# 5_USB3.net
KiCad netlist of a schematic drawn in Altium Designer
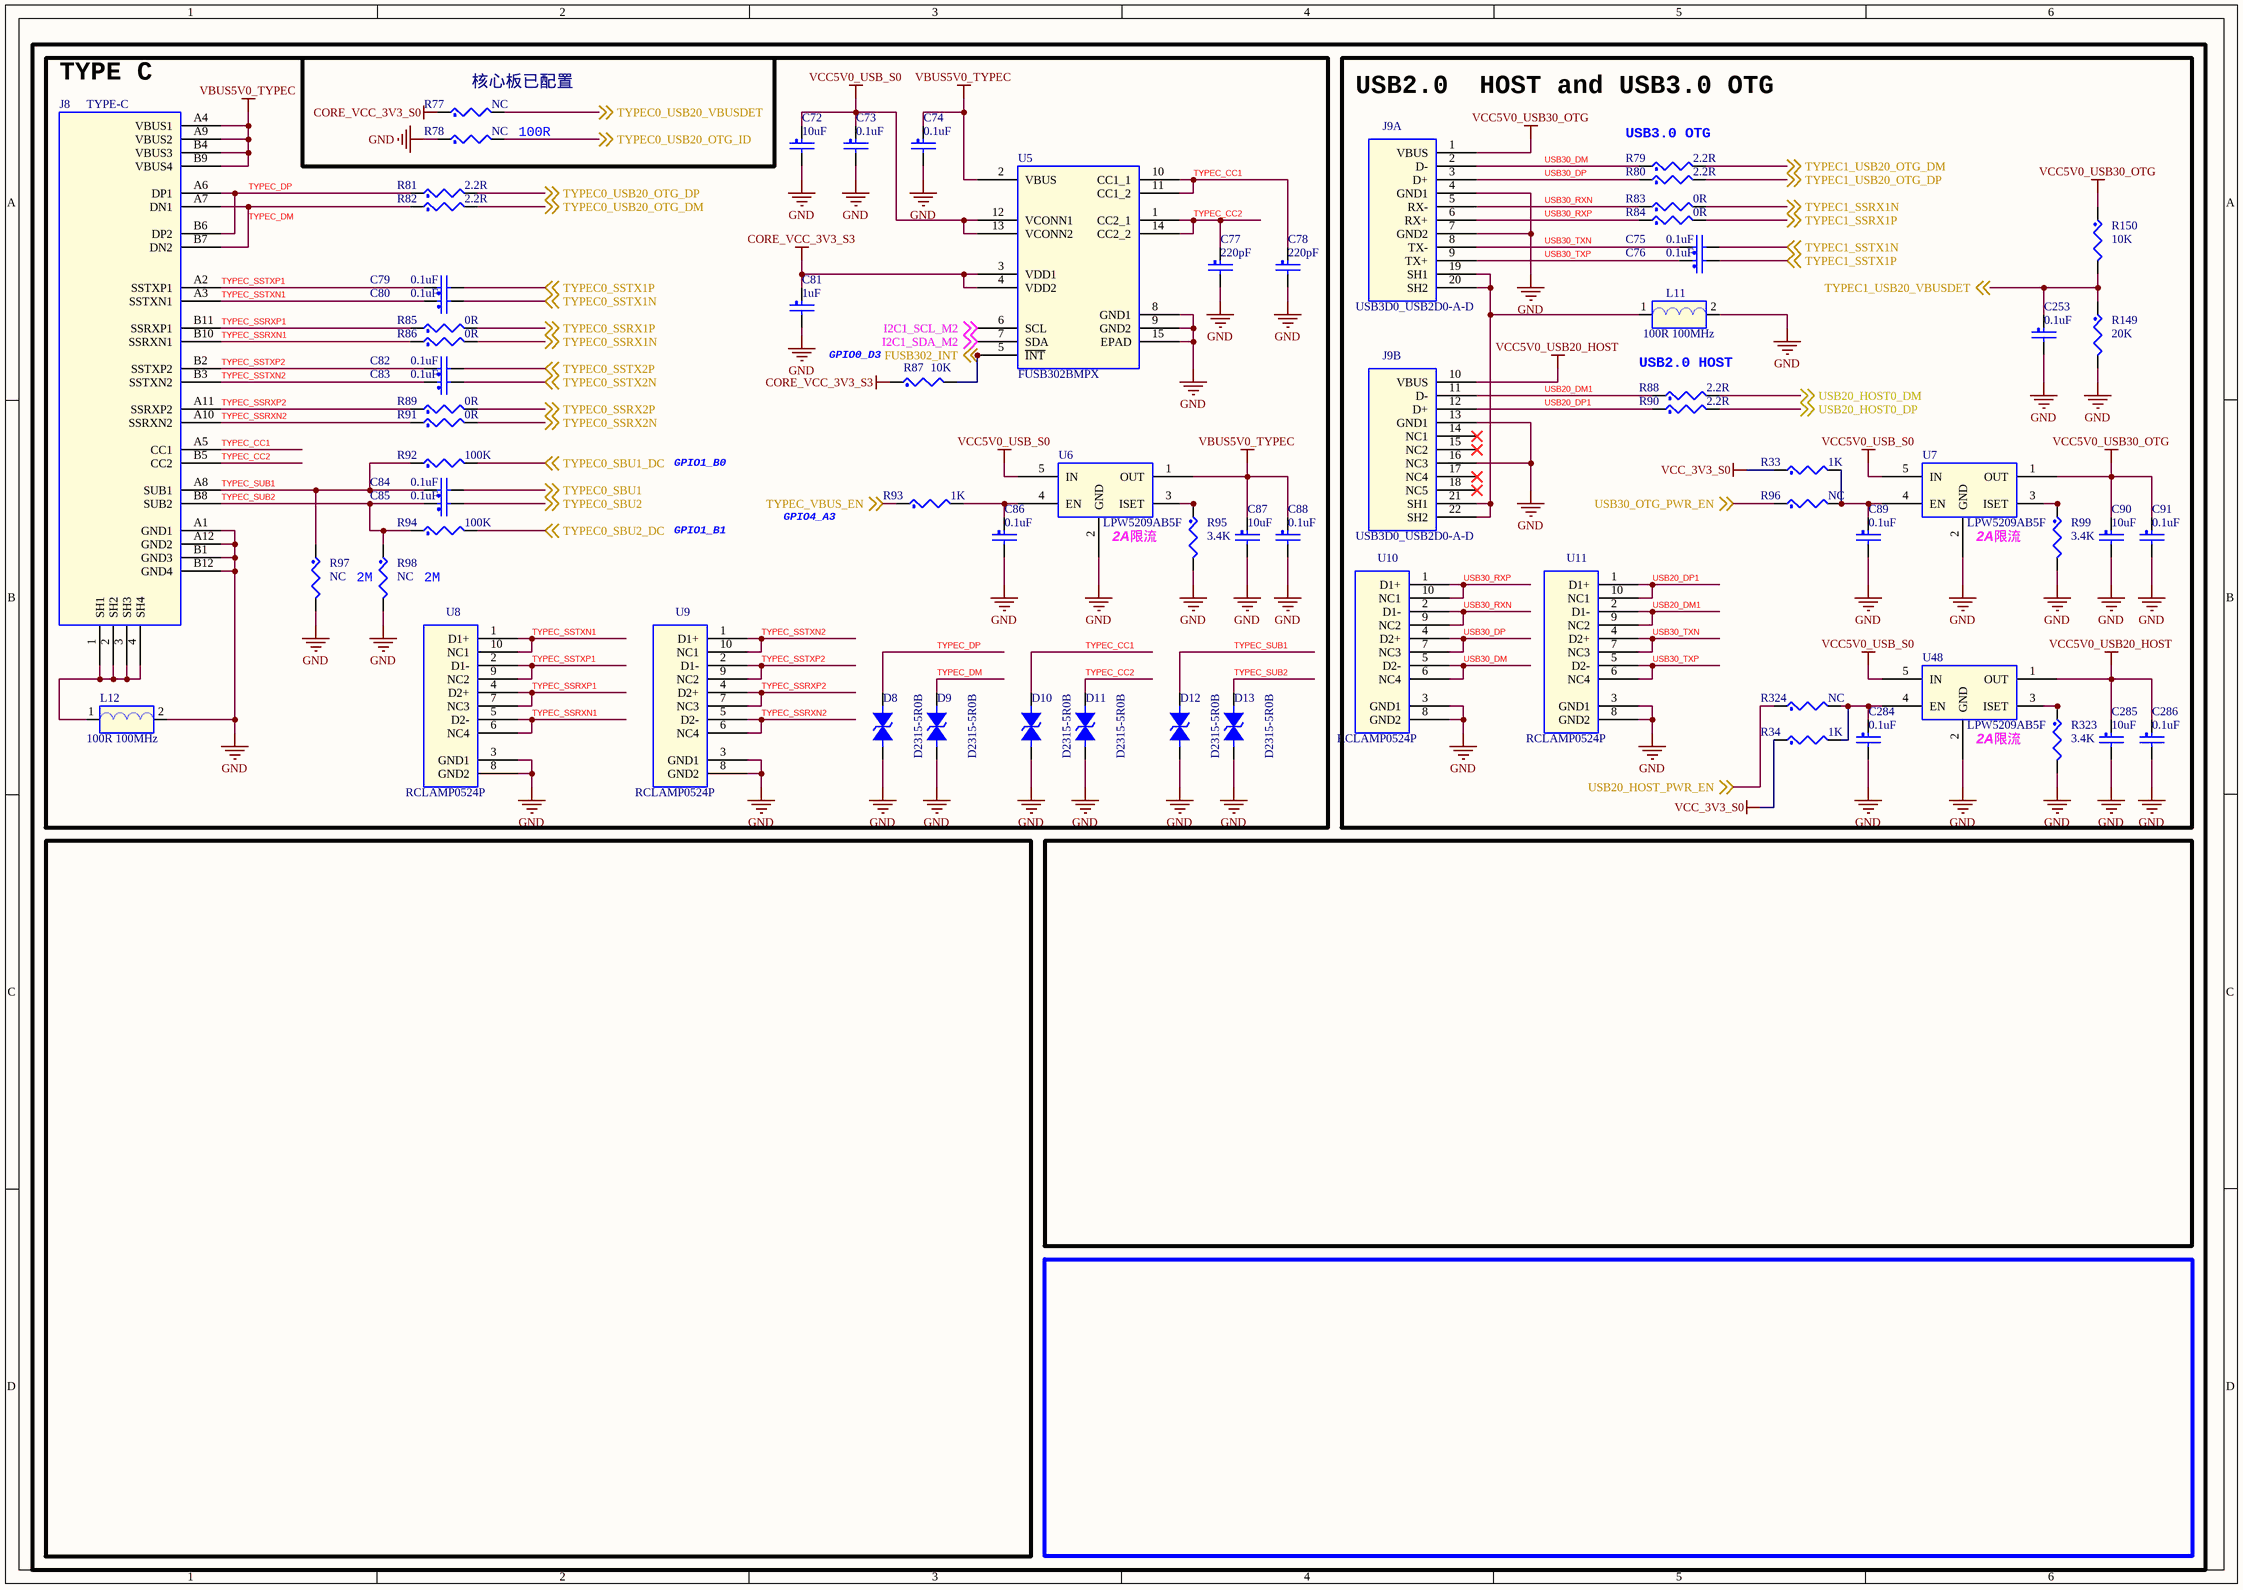
[diagram p0: 5.USB3.SchDoc]

(export (version "E")
  (design (tool "Eeschema 10.0.6"))
  (components
    (comp (ref "C72") (value "10uF") (footprint "0.PCB1:C0402") (libsource (lib "RK3588底板") (part "CAP_NP")))
    (comp (ref "C73") (value "0.1uF") (footprint "0.PCB1:C0402") (libsource (lib "RK3588底板") (part "CAP_NP")))
    (comp (ref "C74") (value "0.1uF") (footprint "0.PCB1:C0402") (libsource (lib "RK3588底板") (part "CAP_NP")))
    (comp (ref "C75") (value "0.1uF") (footprint "0.PCB1:C0402") (libsource (lib "RK3588底板") (part "CAP_NP")))
    (comp (ref "C76") (value "0.1uF") (footprint "0.PCB1:C0402") (libsource (lib "RK3588底板") (part "CAP_NP")))
    (comp (ref "C77") (value "220pF") (footprint "0.PCB1:C0402") (libsource (lib "RK3588底板") (part "CAP_NP")))
    (comp (ref "C78") (value "220pF") (footprint "0.PCB1:C0402") (libsource (lib "RK3588底板") (part "CAP_NP")))
    (comp (ref "C79") (value "0.1uF") (footprint "0.PCB1:C0402") (libsource (lib "RK3588底板") (part "CAP_NP")))
    (comp (ref "C80") (value "0.1uF") (footprint "0.PCB1:C0402") (libsource (lib "RK3588底板") (part "CAP_NP")))
    (comp (ref "C81") (value "1uF") (footprint "0.PCB1:C0402") (libsource (lib "RK3588底板") (part "CAP_NP")))
    (comp (ref "C82") (value "0.1uF") (footprint "0.PCB1:C0402") (libsource (lib "RK3588底板") (part "CAP_NP")))
    (comp (ref "C83") (value "0.1uF") (footprint "0.PCB1:C0402") (libsource (lib "RK3588底板") (part "CAP_NP")))
    (comp (ref "C84") (value "0.1uF") (footprint "0.PCB1:C0402") (libsource (lib "RK3588底板") (part "CAP_NP")))
    (comp (ref "C85") (value "0.1uF") (footprint "0.PCB1:C0402") (libsource (lib "RK3588底板") (part "CAP_NP")))
    (comp (ref "C86") (value "0.1uF") (footprint "0.PCB1:C0402") (libsource (lib "RK3588底板") (part "CAP_NP")))
    (comp (ref "C87") (value "10uF") (footprint "0.PCB1:C0402") (libsource (lib "RK3588底板") (part "CAP_NP")))
    (comp (ref "C88") (value "0.1uF") (footprint "0.PCB1:C0402") (libsource (lib "RK3588底板") (part "CAP_NP")))
    (comp (ref "C89") (value "0.1uF") (footprint "0.PCB1:C0402") (libsource (lib "RK3588底板") (part "CAP_NP")))
    (comp (ref "C90") (value "10uF") (footprint "0.PCB1:C0402") (libsource (lib "RK3588底板") (part "CAP_NP")))
    (comp (ref "C91") (value "0.1uF") (footprint "0.PCB1:C0402") (libsource (lib "RK3588底板") (part "CAP_NP")))
    (comp (ref "C253")
      (value "0.1uF")
      (footprint "0.PCB1:C0402")
      (libsource (lib "RK3588底板") (part "CAP_NP"))
    )
    (comp (ref "C284")
      (value "0.1uF")
      (footprint "0.PCB1:C0402")
      (libsource (lib "RK3588底板") (part "CAP_NP"))
    )
    (comp (ref "C285") (value "10uF") (footprint "0.PCB1:C0402") (libsource (lib "RK3588底板") (part "CAP_NP")))
    (comp (ref "C286")
      (value "0.1uF")
      (footprint "0.PCB1:C0402")
      (libsource (lib "RK3588底板") (part "CAP_NP"))
    )
    (comp (ref "D8")
      (value "D2315-5R0B")
      (footprint "0.PCB1:esd0402")
      (libsource (lib "RK3588底板") (part "DIODE BI-DIR TRIG"))
    )
    (comp (ref "D9")
      (value "D2315-5R0B")
      (footprint "0.PCB1:esd0402")
      (libsource (lib "RK3588底板") (part "DIODE BI-DIR TRIG"))
    )
    (comp (ref "D10")
      (value "D2315-5R0B")
      (footprint "0.PCB1:esd0402")
      (libsource (lib "RK3588底板") (part "DIODE BI-DIR TRIG"))
    )
    (comp (ref "D11")
      (value "D2315-5R0B")
      (footprint "0.PCB1:esd0402")
      (libsource (lib "RK3588底板") (part "DIODE BI-DIR TRIG"))
    )
    (comp (ref "D12")
      (value "D2315-5R0B")
      (footprint "0.PCB1:esd0402")
      (libsource (lib "RK3588底板") (part "DIODE BI-DIR TRIG"))
    )
    (comp (ref "D13")
      (value "D2315-5R0B")
      (footprint "0.PCB1:esd0402")
      (libsource (lib "RK3588底板") (part "DIODE BI-DIR TRIG"))
    )
    (comp (ref "J8")
      (value "TYPE-C")
      (footprint "0.PCB1:usb-c-smd_tyc-324g")
      (libsource (lib "RK3588底板") (part "TYPE-C-24P"))
    )
    (comp (ref "J9")
      (value "USB3D0_USB2D0-A-D")
      (footprint "0.PCB1:USB3D0-AF-18P")
      (libsource (lib "RK3588底板") (part "USB3D0_USB2D0-A-D"))
    )
    (comp (ref "L11")
      (value "100R 100MHz")
      (footprint "0.PCB1:L0603")
      (libsource (lib "RK3588底板") (part "BEAD"))
    )
    (comp (ref "L12")
      (value "100R 100MHz")
      (footprint "0.PCB1:L0603")
      (libsource (lib "RK3588底板") (part "BEAD"))
    )
    (comp (ref "R33") (value "1K") (footprint "0.PCB1:R0402") (libsource (lib "RK3588底板") (part "RES")))
    (comp (ref "R34") (value "1K") (footprint "0.PCB1:R0402") (libsource (lib "RK3588底板") (part "RES")))
    (comp (ref "R77") (value "NC") (footprint "0.PCB1:R0402") (libsource (lib "RK3588底板") (part "RES")))
    (comp (ref "R78") (value "NC") (footprint "0.PCB1:R0402") (libsource (lib "RK3588底板") (part "RES")))
    (comp (ref "R79") (value "2.2R") (footprint "0.PCB1:R0402") (libsource (lib "RK3588底板") (part "RES")))
    (comp (ref "R80") (value "2.2R") (footprint "0.PCB1:R0402") (libsource (lib "RK3588底板") (part "RES")))
    (comp (ref "R81") (value "2.2R") (footprint "0.PCB1:R0402") (libsource (lib "RK3588底板") (part "RES")))
    (comp (ref "R82") (value "2.2R") (footprint "0.PCB1:R0402") (libsource (lib "RK3588底板") (part "RES")))
    (comp (ref "R83") (value "0R") (footprint "0.PCB1:R0402") (libsource (lib "RK3588底板") (part "RES")))
    (comp (ref "R84") (value "0R") (footprint "0.PCB1:R0402") (libsource (lib "RK3588底板") (part "RES")))
    (comp (ref "R85") (value "0R") (footprint "0.PCB1:R0402") (libsource (lib "RK3588底板") (part "RES")))
    (comp (ref "R86") (value "0R") (footprint "0.PCB1:R0402") (libsource (lib "RK3588底板") (part "RES")))
    (comp (ref "R87") (value "10K") (footprint "0.PCB1:R0402") (libsource (lib "RK3588底板") (part "RES")))
    (comp (ref "R88") (value "2.2R") (footprint "0.PCB1:R0402") (libsource (lib "RK3588底板") (part "RES")))
    (comp (ref "R89") (value "0R") (footprint "0.PCB1:R0402") (libsource (lib "RK3588底板") (part "RES")))
    (comp (ref "R90") (value "2.2R") (footprint "0.PCB1:R0402") (libsource (lib "RK3588底板") (part "RES")))
    (comp (ref "R91") (value "0R") (footprint "0.PCB1:R0402") (libsource (lib "RK3588底板") (part "RES")))
    (comp (ref "R92") (value "100K") (footprint "0.PCB1:R0402") (libsource (lib "RK3588底板") (part "RES")))
    (comp (ref "R93") (value "1K") (footprint "0.PCB1:R0402") (libsource (lib "RK3588底板") (part "RES")))
    (comp (ref "R94") (value "100K") (footprint "0.PCB1:R0402") (libsource (lib "RK3588底板") (part "RES")))
    (comp (ref "R95") (value "3.4K") (footprint "0.PCB1:R0402") (libsource (lib "RK3588底板") (part "RES")))
    (comp (ref "R96") (value "NC") (footprint "0.PCB1:R0402") (libsource (lib "RK3588底板") (part "RES")))
    (comp (ref "R97") (value "NC") (footprint "0.PCB1:R0402") (libsource (lib "RK3588底板") (part "RES")))
    (comp (ref "R98") (value "NC") (footprint "0.PCB1:R0402") (libsource (lib "RK3588底板") (part "RES")))
    (comp (ref "R99") (value "3.4K") (footprint "0.PCB1:R0402") (libsource (lib "RK3588底板") (part "RES")))
    (comp (ref "R149") (value "20K") (footprint "0.PCB1:R0402") (libsource (lib "RK3588底板") (part "RES")))
    (comp (ref "R150") (value "10K") (footprint "0.PCB1:R0402") (libsource (lib "RK3588底板") (part "RES")))
    (comp (ref "R323") (value "3.4K") (footprint "0.PCB1:R0402") (libsource (lib "RK3588底板") (part "RES")))
    (comp (ref "R324") (value "NC") (footprint "0.PCB1:R0402") (libsource (lib "RK3588底板") (part "RES")))
    (comp (ref "U5")
      (value "FUSB302BMPX")
      (footprint "0.PCB1:WQFN14-0R50-2R5X2R5EP1R45X1R45")
      (libsource (lib "RK3588底板") (part "FUSB302BMPX"))
    )
    (comp (ref "U6")
      (value "LPW5209AB5F")
      (footprint "0.PCB1:SOT23-5")
      (libsource (lib "RK3588底板") (part "LPW5209AB5F"))
    )
    (comp (ref "U7")
      (value "LPW5209AB5F")
      (footprint "0.PCB1:SOT23-5")
      (libsource (lib "RK3588底板") (part "LPW5209AB5F"))
    )
    (comp (ref "U8")
      (value "RCLAMP0524P")
      (footprint "0.PCB1:USON_10")
      (libsource (lib "RK3588底板") (part "RCLAMP0524P"))
    )
    (comp (ref "U9")
      (value "RCLAMP0524P")
      (footprint "0.PCB1:USON_10")
      (libsource (lib "RK3588底板") (part "RCLAMP0524P"))
    )
    (comp (ref "U10")
      (value "RCLAMP0524P")
      (footprint "0.PCB1:USON_10")
      (libsource (lib "RK3588底板") (part "RCLAMP0524P"))
    )
    (comp (ref "U11")
      (value "RCLAMP0524P")
      (footprint "0.PCB1:USON_10")
      (libsource (lib "RK3588底板") (part "RCLAMP0524P"))
    )
    (comp (ref "U48")
      (value "LPW5209AB5F")
      (footprint "0.PCB1:SOT23-5")
      (libsource (lib "RK3588底板") (part "LPW5209AB5F"))
    )
  )
  (nets
    (net (code "1") (name "/TYPEC_CC1") (class "Default")
      (node (ref "C78") (pin "1") (pinfunction "1_1") (pintype "passive"))
      (node (ref "D10") (pin "2") (pinfunction "2_2") (pintype "passive"))
      (node (ref "J8") (pin "A5") (pinfunction "CC1_A5") (pintype "passive"))
      (node (ref "U5") (pin "10") (pinfunction "CC1_1_10") (pintype "passive"))
      (node (ref "U5") (pin "11") (pinfunction "CC1_2_11") (pintype "passive"))
    )
    (net (code "2") (name "/TYPEC_CC2") (class "Default")
      (node (ref "C77") (pin "1") (pinfunction "1_1") (pintype "passive"))
      (node (ref "D11") (pin "2") (pinfunction "2_2") (pintype "passive"))
      (node (ref "J8") (pin "B5") (pinfunction "CC2_B5") (pintype "passive"))
      (node (ref "U5") (pin "1") (pinfunction "CC2_1_1") (pintype "passive"))
      (node (ref "U5") (pin "14") (pinfunction "CC2_2_14") (pintype "passive"))
    )
    (net (code "3") (name "/TYPEC_DM") (class "Default")
      (node (ref "D9") (pin "2") (pinfunction "2_2") (pintype "passive"))
      (node (ref "J8") (pin "A7") (pinfunction "DN1_A7") (pintype "passive"))
      (node (ref "J8") (pin "B7") (pinfunction "DN2_B7") (pintype "passive"))
      (node (ref "R82") (pin "1") (pinfunction "1_1") (pintype "passive"))
    )
    (net (code "4") (name "/TYPEC_DP") (class "Default")
      (node (ref "D8") (pin "2") (pinfunction "2_2") (pintype "passive"))
      (node (ref "J8") (pin "A6") (pinfunction "DP1_A6") (pintype "passive"))
      (node (ref "J8") (pin "B6") (pinfunction "DP2_B6") (pintype "passive"))
      (node (ref "R81") (pin "1") (pinfunction "1_1") (pintype "passive"))
    )
    (net (code "5") (name "/TYPEC_SSRXN1") (class "Default")
      (node (ref "J8") (pin "B10") (pinfunction "SSRXN1_B10") (pintype "passive"))
      (node (ref "R86") (pin "1") (pinfunction "1_1") (pintype "passive"))
      (node (ref "U8") (pin "5") (pinfunction "D2-_5") (pintype "passive"))
      (node (ref "U8") (pin "6") (pinfunction "NC4_6") (pintype "passive"))
    )
    (net (code "6") (name "/TYPEC_SSRXN2") (class "Default")
      (node (ref "J8") (pin "A10") (pinfunction "SSRXN2_A10") (pintype "passive"))
      (node (ref "R91") (pin "1") (pinfunction "1_1") (pintype "passive"))
      (node (ref "U9") (pin "5") (pinfunction "D2-_5") (pintype "passive"))
      (node (ref "U9") (pin "6") (pinfunction "NC4_6") (pintype "passive"))
    )
    (net (code "7") (name "/TYPEC_SSRXP1") (class "Default")
      (node (ref "J8") (pin "B11") (pinfunction "SSRXP1_B11") (pintype "passive"))
      (node (ref "R85") (pin "1") (pinfunction "1_1") (pintype "passive"))
      (node (ref "U8") (pin "4") (pinfunction "D2+_4") (pintype "passive"))
      (node (ref "U8") (pin "7") (pinfunction "NC3_7") (pintype "passive"))
    )
    (net (code "8") (name "/TYPEC_SSRXP2") (class "Default")
      (node (ref "J8") (pin "A11") (pinfunction "SSRXP2_A11") (pintype "passive"))
      (node (ref "R89") (pin "1") (pinfunction "1_1") (pintype "passive"))
      (node (ref "U9") (pin "4") (pinfunction "D2+_4") (pintype "passive"))
      (node (ref "U9") (pin "7") (pinfunction "NC3_7") (pintype "passive"))
    )
    (net (code "9") (name "/TYPEC_SSTXN1") (class "Default")
      (node (ref "C80") (pin "1") (pinfunction "1_1") (pintype "passive"))
      (node (ref "J8") (pin "A3") (pinfunction "SSTXN1_A3") (pintype "passive"))
      (node (ref "U8") (pin "1") (pinfunction "D1+_1") (pintype "passive"))
      (node (ref "U8") (pin "10") (pinfunction "NC1_10") (pintype "passive"))
    )
    (net (code "10") (name "/TYPEC_SSTXN2") (class "Default")
      (node (ref "C83") (pin "1") (pinfunction "1_1") (pintype "passive"))
      (node (ref "J8") (pin "B3") (pinfunction "SSTXN2_B3") (pintype "passive"))
      (node (ref "U9") (pin "1") (pinfunction "D1+_1") (pintype "passive"))
      (node (ref "U9") (pin "10") (pinfunction "NC1_10") (pintype "passive"))
    )
    (net (code "11") (name "/TYPEC_SSTXP1") (class "Default")
      (node (ref "C79") (pin "1") (pinfunction "1_1") (pintype "passive"))
      (node (ref "J8") (pin "A2") (pinfunction "SSTXP1_A2") (pintype "passive"))
      (node (ref "U8") (pin "2") (pinfunction "D1-_2") (pintype "passive"))
      (node (ref "U8") (pin "9") (pinfunction "NC2_9") (pintype "passive"))
    )
    (net (code "12") (name "/TYPEC_SSTXP2") (class "Default")
      (node (ref "C82") (pin "1") (pinfunction "1_1") (pintype "passive"))
      (node (ref "J8") (pin "B2") (pinfunction "SSTXP2_B2") (pintype "passive"))
      (node (ref "U9") (pin "2") (pinfunction "D1-_2") (pintype "passive"))
      (node (ref "U9") (pin "9") (pinfunction "NC2_9") (pintype "passive"))
    )
    (net (code "13") (name "/TYPEC_SUB1") (class "Default")
      (node (ref "C84") (pin "1") (pinfunction "1_1") (pintype "passive"))
      (node (ref "D12") (pin "2") (pinfunction "2_2") (pintype "passive"))
      (node (ref "J8") (pin "A8") (pinfunction "SUB1_A8") (pintype "passive"))
      (node (ref "R92") (pin "1") (pinfunction "1_1") (pintype "passive"))
      (node (ref "R97") (pin "1") (pinfunction "1_1") (pintype "passive"))
    )
    (net (code "14") (name "/TYPEC_SUB2") (class "Default")
      (node (ref "C85") (pin "1") (pinfunction "1_1") (pintype "passive"))
      (node (ref "D13") (pin "2") (pinfunction "2_2") (pintype "passive"))
      (node (ref "J8") (pin "B8") (pinfunction "SUB2_B8") (pintype "passive"))
      (node (ref "R94") (pin "1") (pinfunction "1_1") (pintype "passive"))
      (node (ref "R98") (pin "1") (pinfunction "1_1") (pintype "passive"))
    )
    (net (code "15") (name "/USB20_DM1") (class "Default")
      (node (ref "J9") (pin "11") (pinfunction "D-_11") (pintype "passive"))
      (node (ref "R88") (pin "1") (pinfunction "1_1") (pintype "passive"))
      (node (ref "U11") (pin "2") (pinfunction "D1-_2") (pintype "passive"))
      (node (ref "U11") (pin "9") (pinfunction "NC2_9") (pintype "passive"))
    )
    (net (code "16") (name "/USB20_DP1") (class "Default")
      (node (ref "J9") (pin "12") (pinfunction "D+_12") (pintype "passive"))
      (node (ref "R90") (pin "1") (pinfunction "1_1") (pintype "passive"))
      (node (ref "U11") (pin "1") (pinfunction "D1+_1") (pintype "passive"))
      (node (ref "U11") (pin "10") (pinfunction "NC1_10") (pintype "passive"))
    )
    (net (code "17") (name "/USB30_DM") (class "Default")
      (node (ref "J9") (pin "2") (pinfunction "D-_2") (pintype "passive"))
      (node (ref "R79") (pin "1") (pinfunction "1_1") (pintype "passive"))
      (node (ref "U10") (pin "5") (pinfunction "D2-_5") (pintype "passive"))
      (node (ref "U10") (pin "6") (pinfunction "NC4_6") (pintype "passive"))
    )
    (net (code "18") (name "/USB30_DP") (class "Default")
      (node (ref "J9") (pin "3") (pinfunction "D+_3") (pintype "passive"))
      (node (ref "R80") (pin "1") (pinfunction "1_1") (pintype "passive"))
      (node (ref "U10") (pin "4") (pinfunction "D2+_4") (pintype "passive"))
      (node (ref "U10") (pin "7") (pinfunction "NC3_7") (pintype "passive"))
    )
    (net (code "19") (name "/USB30_RXN") (class "Default")
      (node (ref "J9") (pin "5") (pinfunction "RX-_5") (pintype "passive"))
      (node (ref "R83") (pin "1") (pinfunction "1_1") (pintype "passive"))
      (node (ref "U10") (pin "2") (pinfunction "D1-_2") (pintype "passive"))
      (node (ref "U10") (pin "9") (pinfunction "NC2_9") (pintype "passive"))
    )
    (net (code "20") (name "/USB30_RXP") (class "Default")
      (node (ref "J9") (pin "6") (pinfunction "RX+_6") (pintype "passive"))
      (node (ref "R84") (pin "1") (pinfunction "1_1") (pintype "passive"))
      (node (ref "U10") (pin "1") (pinfunction "D1+_1") (pintype "passive"))
      (node (ref "U10") (pin "10") (pinfunction "NC1_10") (pintype "passive"))
    )
    (net (code "21") (name "/USB30_TXN") (class "Default")
      (node (ref "C75") (pin "1") (pinfunction "1_1") (pintype "passive"))
      (node (ref "J9") (pin "8") (pinfunction "TX-_8") (pintype "passive"))
      (node (ref "U11") (pin "4") (pinfunction "D2+_4") (pintype "passive"))
      (node (ref "U11") (pin "7") (pinfunction "NC3_7") (pintype "passive"))
    )
    (net (code "22") (name "/USB30_TXP") (class "Default")
      (node (ref "C76") (pin "1") (pinfunction "1_1") (pintype "passive"))
      (node (ref "J9") (pin "9") (pinfunction "TX+_9") (pintype "passive"))
      (node (ref "U11") (pin "5") (pinfunction "D2-_5") (pintype "passive"))
      (node (ref "U11") (pin "6") (pinfunction "NC4_6") (pintype "passive"))
    )
    (net (code "23") (name "CORE_VCC_3V3_S0") (class "Default")
      (node (ref "R77") (pin "1") (pinfunction "1_1") (pintype "passive"))
    )
    (net (code "24") (name "CORE_VCC_3V3_S3") (class "Default")
      (node (ref "C81") (pin "1") (pinfunction "1_1") (pintype "passive"))
      (node (ref "R87") (pin "1") (pinfunction "1_1") (pintype "passive"))
      (node (ref "U5") (pin "3") (pinfunction "VDD1_3") (pintype "passive"))
      (node (ref "U5") (pin "4") (pinfunction "VDD2_4") (pintype "passive"))
    )
    (net (code "25") (name "FUSB302_INT") (class "Default")
      (node (ref "R87") (pin "2") (pinfunction "2_2") (pintype "passive"))
      (node (ref "U5") (pin "5") (pinfunction "~{INT}_5") (pintype "passive"))
    )
    (net (code "26") (name "GND") (class "Default")
      (node (ref "C253") (pin "2") (pinfunction "2_2") (pintype "passive"))
      (node (ref "C284") (pin "2") (pinfunction "2_2") (pintype "passive"))
      (node (ref "C285") (pin "2") (pinfunction "2_2") (pintype "passive"))
      (node (ref "C286") (pin "2") (pinfunction "2_2") (pintype "passive"))
      (node (ref "C72") (pin "2") (pinfunction "2_2") (pintype "passive"))
      (node (ref "C73") (pin "2") (pinfunction "2_2") (pintype "passive"))
      (node (ref "C74") (pin "2") (pinfunction "2_2") (pintype "passive"))
      (node (ref "C77") (pin "2") (pinfunction "2_2") (pintype "passive"))
      (node (ref "C78") (pin "2") (pinfunction "2_2") (pintype "passive"))
      (node (ref "C81") (pin "2") (pinfunction "2_2") (pintype "passive"))
      (node (ref "C86") (pin "2") (pinfunction "2_2") (pintype "passive"))
      (node (ref "C87") (pin "2") (pinfunction "2_2") (pintype "passive"))
      (node (ref "C88") (pin "2") (pinfunction "2_2") (pintype "passive"))
      (node (ref "C89") (pin "2") (pinfunction "2_2") (pintype "passive"))
      (node (ref "C90") (pin "2") (pinfunction "2_2") (pintype "passive"))
      (node (ref "C91") (pin "2") (pinfunction "2_2") (pintype "passive"))
      (node (ref "D10") (pin "1") (pinfunction "1_1") (pintype "passive"))
      (node (ref "D11") (pin "1") (pinfunction "1_1") (pintype "passive"))
      (node (ref "D12") (pin "1") (pinfunction "1_1") (pintype "passive"))
      (node (ref "D13") (pin "1") (pinfunction "1_1") (pintype "passive"))
      (node (ref "D8") (pin "1") (pinfunction "1_1") (pintype "passive"))
      (node (ref "D9") (pin "1") (pinfunction "1_1") (pintype "passive"))
      (node (ref "J8") (pin "A1") (pinfunction "GND1_A1") (pintype "passive"))
      (node (ref "J8") (pin "A12") (pinfunction "GND2_A12") (pintype "passive"))
      (node (ref "J8") (pin "B1") (pinfunction "GND3_B1") (pintype "passive"))
      (node (ref "J8") (pin "B12") (pinfunction "GND4_B12") (pintype "passive"))
      (node (ref "J9") (pin "13") (pinfunction "GND1_13") (pintype "passive"))
      (node (ref "J9") (pin "16") (pinfunction "NC3_16") (pintype "passive"))
      (node (ref "J9") (pin "4") (pinfunction "GND1_4") (pintype "passive"))
      (node (ref "J9") (pin "7") (pinfunction "GND2_7") (pintype "passive"))
      (node (ref "L11") (pin "2") (pinfunction "2_2") (pintype "passive"))
      (node (ref "L12") (pin "2") (pinfunction "2_2") (pintype "passive"))
      (node (ref "R149") (pin "2") (pinfunction "2_2") (pintype "passive"))
      (node (ref "R323") (pin "2") (pinfunction "2_2") (pintype "passive"))
      (node (ref "R78") (pin "1") (pinfunction "1_1") (pintype "passive"))
      (node (ref "R95") (pin "2") (pinfunction "2_2") (pintype "passive"))
      (node (ref "R97") (pin "2") (pinfunction "2_2") (pintype "passive"))
      (node (ref "R98") (pin "2") (pinfunction "2_2") (pintype "passive"))
      (node (ref "R99") (pin "2") (pinfunction "2_2") (pintype "passive"))
      (node (ref "U10") (pin "3") (pinfunction "GND1_3") (pintype "passive"))
      (node (ref "U10") (pin "8") (pinfunction "GND2_8") (pintype "passive"))
      (node (ref "U11") (pin "3") (pinfunction "GND1_3") (pintype "passive"))
      (node (ref "U11") (pin "8") (pinfunction "GND2_8") (pintype "passive"))
      (node (ref "U48") (pin "2") (pinfunction "GND_2") (pintype "passive"))
      (node (ref "U5") (pin "15") (pinfunction "EPAD_15") (pintype "passive"))
      (node (ref "U5") (pin "8") (pinfunction "GND1_8") (pintype "passive"))
      (node (ref "U5") (pin "9") (pinfunction "GND2_9") (pintype "passive"))
      (node (ref "U6") (pin "2") (pinfunction "GND_2") (pintype "passive"))
      (node (ref "U7") (pin "2") (pinfunction "GND_2") (pintype "passive"))
      (node (ref "U8") (pin "3") (pinfunction "GND1_3") (pintype "passive"))
      (node (ref "U8") (pin "8") (pinfunction "GND2_8") (pintype "passive"))
      (node (ref "U9") (pin "3") (pinfunction "GND1_3") (pintype "passive"))
      (node (ref "U9") (pin "8") (pinfunction "GND2_8") (pintype "passive"))
    )
    (net (code "27") (name "I2C1_SCL_M2") (class "Default")
      (node (ref "U5") (pin "6") (pinfunction "SCL_6") (pintype "passive"))
    )
    (net (code "28") (name "I2C1_SDA_M2") (class "Default")
      (node (ref "U5") (pin "7") (pinfunction "SDA_7") (pintype "passive"))
    )
    (net (code "29") (name "Net-(J8-SH1)") (class "Default")
      (node (ref "J8") (pin "1") (pinfunction "SH1_1") (pintype "passive"))
      (node (ref "J8") (pin "2") (pinfunction "SH2_2") (pintype "passive"))
      (node (ref "J8") (pin "3") (pinfunction "SH3_3") (pintype "passive"))
      (node (ref "J8") (pin "4") (pinfunction "SH4_4") (pintype "passive"))
      (node (ref "L12") (pin "1") (pinfunction "1_1") (pintype "passive"))
    )
    (net (code "30") (name "Net-(J9A-SH1)") (class "Default")
      (node (ref "J9") (pin "19") (pinfunction "SH1_19") (pintype "passive"))
      (node (ref "J9") (pin "20") (pinfunction "SH2_20") (pintype "passive"))
      (node (ref "J9") (pin "21") (pinfunction "SH1_21") (pintype "passive"))
      (node (ref "J9") (pin "22") (pinfunction "SH2_22") (pintype "passive"))
      (node (ref "L11") (pin "1") (pinfunction "1_1") (pintype "passive"))
    )
    (net (code "31") (name "Net-(U6-EN)") (class "Default")
      (node (ref "C86") (pin "1") (pinfunction "1_1") (pintype "passive"))
      (node (ref "R93") (pin "2") (pinfunction "2_2") (pintype "passive"))
      (node (ref "U6") (pin "4") (pinfunction "EN_4") (pintype "passive"))
    )
    (net (code "32") (name "Net-(U6-ISET)") (class "Default")
      (node (ref "R95") (pin "1") (pinfunction "1_1") (pintype "passive"))
      (node (ref "U6") (pin "3") (pinfunction "ISET_3") (pintype "passive"))
    )
    (net (code "33") (name "Net-(U7-EN)") (class "Default")
      (node (ref "C89") (pin "1") (pinfunction "1_1") (pintype "passive"))
      (node (ref "R33") (pin "2") (pinfunction "2_2") (pintype "passive"))
      (node (ref "R96") (pin "2") (pinfunction "2_2") (pintype "passive"))
      (node (ref "U7") (pin "4") (pinfunction "EN_4") (pintype "passive"))
    )
    (net (code "34") (name "Net-(U7-ISET)") (class "Default")
      (node (ref "R99") (pin "1") (pinfunction "1_1") (pintype "passive"))
      (node (ref "U7") (pin "3") (pinfunction "ISET_3") (pintype "passive"))
    )
    (net (code "35") (name "Net-(U48-EN)") (class "Default")
      (node (ref "C284") (pin "1") (pinfunction "1_1") (pintype "passive"))
      (node (ref "R324") (pin "2") (pinfunction "2_2") (pintype "passive"))
      (node (ref "R34") (pin "2") (pinfunction "2_2") (pintype "passive"))
      (node (ref "U48") (pin "4") (pinfunction "EN_4") (pintype "passive"))
    )
    (net (code "36") (name "Net-(U48-ISET)") (class "Default")
      (node (ref "R323") (pin "1") (pinfunction "1_1") (pintype "passive"))
      (node (ref "U48") (pin "3") (pinfunction "ISET_3") (pintype "passive"))
    )
    (net (code "37") (name "TYPEC0_SBU1") (class "Default")
      (node (ref "C84") (pin "2") (pinfunction "2_2") (pintype "passive"))
    )
    (net (code "38") (name "TYPEC0_SBU1_DC") (class "Default")
      (node (ref "R92") (pin "2") (pinfunction "2_2") (pintype "passive"))
    )
    (net (code "39") (name "TYPEC0_SBU2") (class "Default")
      (node (ref "C85") (pin "2") (pinfunction "2_2") (pintype "passive"))
    )
    (net (code "40") (name "TYPEC0_SBU2_DC") (class "Default")
      (node (ref "R94") (pin "2") (pinfunction "2_2") (pintype "passive"))
    )
    (net (code "41") (name "TYPEC0_SSRX1N") (class "Default")
      (node (ref "R86") (pin "2") (pinfunction "2_2") (pintype "passive"))
    )
    (net (code "42") (name "TYPEC0_SSRX1P") (class "Default")
      (node (ref "R85") (pin "2") (pinfunction "2_2") (pintype "passive"))
    )
    (net (code "43") (name "TYPEC0_SSRX2N") (class "Default")
      (node (ref "R91") (pin "2") (pinfunction "2_2") (pintype "passive"))
    )
    (net (code "44") (name "TYPEC0_SSRX2P") (class "Default")
      (node (ref "R89") (pin "2") (pinfunction "2_2") (pintype "passive"))
    )
    (net (code "45") (name "TYPEC0_SSTX1N") (class "Default")
      (node (ref "C80") (pin "2") (pinfunction "2_2") (pintype "passive"))
    )
    (net (code "46") (name "TYPEC0_SSTX1P") (class "Default")
      (node (ref "C79") (pin "2") (pinfunction "2_2") (pintype "passive"))
    )
    (net (code "47") (name "TYPEC0_SSTX2N") (class "Default")
      (node (ref "C83") (pin "2") (pinfunction "2_2") (pintype "passive"))
    )
    (net (code "48") (name "TYPEC0_SSTX2P") (class "Default")
      (node (ref "C82") (pin "2") (pinfunction "2_2") (pintype "passive"))
    )
    (net (code "49") (name "TYPEC0_USB20_OTG_DM") (class "Default")
      (node (ref "R82") (pin "2") (pinfunction "2_2") (pintype "passive"))
    )
    (net (code "50") (name "TYPEC0_USB20_OTG_DP") (class "Default")
      (node (ref "R81") (pin "2") (pinfunction "2_2") (pintype "passive"))
    )
    (net (code "51") (name "TYPEC0_USB20_OTG_ID") (class "Default")
      (node (ref "R78") (pin "2") (pinfunction "2_2") (pintype "passive"))
    )
    (net (code "52") (name "TYPEC0_USB20_VBUSDET") (class "Default")
      (node (ref "R77") (pin "2") (pinfunction "2_2") (pintype "passive"))
    )
    (net (code "53") (name "TYPEC1_SSRX1N") (class "Default")
      (node (ref "R83") (pin "2") (pinfunction "2_2") (pintype "passive"))
    )
    (net (code "54") (name "TYPEC1_SSRX1P") (class "Default")
      (node (ref "R84") (pin "2") (pinfunction "2_2") (pintype "passive"))
    )
    (net (code "55") (name "TYPEC1_SSTX1N") (class "Default")
      (node (ref "C75") (pin "2") (pinfunction "2_2") (pintype "passive"))
    )
    (net (code "56") (name "TYPEC1_SSTX1P") (class "Default")
      (node (ref "C76") (pin "2") (pinfunction "2_2") (pintype "passive"))
    )
    (net (code "57") (name "TYPEC1_USB20_OTG_DM") (class "Default")
      (node (ref "R79") (pin "2") (pinfunction "2_2") (pintype "passive"))
    )
    (net (code "58") (name "TYPEC1_USB20_OTG_DP") (class "Default")
      (node (ref "R80") (pin "2") (pinfunction "2_2") (pintype "passive"))
    )
    (net (code "59") (name "TYPEC1_USB20_VBUSDET") (class "Default")
      (node (ref "C253") (pin "1") (pinfunction "1_1") (pintype "passive"))
      (node (ref "R149") (pin "1") (pinfunction "1_1") (pintype "passive"))
      (node (ref "R150") (pin "2") (pinfunction "2_2") (pintype "passive"))
    )
    (net (code "60") (name "TYPEC_VBUS_EN") (class "Default")
      (node (ref "R93") (pin "1") (pinfunction "1_1") (pintype "passive"))
    )
    (net (code "61") (name "USB20_HOST0_DM") (class "Default")
      (node (ref "R88") (pin "2") (pinfunction "2_2") (pintype "passive"))
    )
    (net (code "62") (name "USB20_HOST0_DP") (class "Default")
      (node (ref "R90") (pin "2") (pinfunction "2_2") (pintype "passive"))
    )
    (net (code "63") (name "USB20_HOST_PWR_EN") (class "Default")
      (node (ref "R324") (pin "1") (pinfunction "1_1") (pintype "passive"))
    )
    (net (code "64") (name "USB30_OTG_PWR_EN") (class "Default")
      (node (ref "R96") (pin "1") (pinfunction "1_1") (pintype "passive"))
    )
    (net (code "65") (name "VBUS5V0_TYPEC") (class "Default")
      (node (ref "C74") (pin "1") (pinfunction "1_1") (pintype "passive"))
      (node (ref "C87") (pin "1") (pinfunction "1_1") (pintype "passive"))
      (node (ref "C88") (pin "1") (pinfunction "1_1") (pintype "passive"))
      (node (ref "J8") (pin "A4") (pinfunction "VBUS1_A4") (pintype "passive"))
      (node (ref "J8") (pin "A9") (pinfunction "VBUS2_A9") (pintype "passive"))
      (node (ref "J8") (pin "B4") (pinfunction "VBUS3_B4") (pintype "passive"))
      (node (ref "J8") (pin "B9") (pinfunction "VBUS4_B9") (pintype "passive"))
      (node (ref "U5") (pin "2") (pinfunction "VBUS_2") (pintype "passive"))
      (node (ref "U6") (pin "1") (pinfunction "OUT_1") (pintype "passive"))
    )
    (net (code "66") (name "VCC5V0_USB20_HOST") (class "Default")
      (node (ref "C285") (pin "1") (pinfunction "1_1") (pintype "passive"))
      (node (ref "C286") (pin "1") (pinfunction "1_1") (pintype "passive"))
      (node (ref "J9") (pin "10") (pinfunction "VBUS_10") (pintype "passive"))
      (node (ref "U48") (pin "1") (pinfunction "OUT_1") (pintype "passive"))
    )
    (net (code "67") (name "VCC5V0_USB30_OTG") (class "Default")
      (node (ref "C90") (pin "1") (pinfunction "1_1") (pintype "passive"))
      (node (ref "C91") (pin "1") (pinfunction "1_1") (pintype "passive"))
      (node (ref "J9") (pin "1") (pinfunction "VBUS_1") (pintype "passive"))
      (node (ref "R150") (pin "1") (pinfunction "1_1") (pintype "passive"))
      (node (ref "U7") (pin "1") (pinfunction "OUT_1") (pintype "passive"))
    )
    (net (code "68") (name "VCC5V0_USB_S0") (class "Default")
      (node (ref "C72") (pin "1") (pinfunction "1_1") (pintype "passive"))
      (node (ref "C73") (pin "1") (pinfunction "1_1") (pintype "passive"))
      (node (ref "U48") (pin "5") (pinfunction "IN_5") (pintype "passive"))
      (node (ref "U5") (pin "12") (pinfunction "VCONN1_12") (pintype "passive"))
      (node (ref "U5") (pin "13") (pinfunction "VCONN2_13") (pintype "passive"))
      (node (ref "U6") (pin "5") (pinfunction "IN_5") (pintype "passive"))
      (node (ref "U7") (pin "5") (pinfunction "IN_5") (pintype "passive"))
    )
    (net (code "69") (name "VCC_3V3_S0") (class "Default")
      (node (ref "R33") (pin "1") (pinfunction "1_1") (pintype "passive"))
      (node (ref "R34") (pin "1") (pinfunction "1_1") (pintype "passive"))
    )
    (net (code "70") (name "unconnected-(J9B-NC1-Pad14)") (class "Default")
      (node (ref "J9") (pin "14") (pinfunction "NC1_14") (pintype "passive+no_connect"))
    )
    (net (code "71") (name "unconnected-(J9B-NC2-Pad15)") (class "Default")
      (node (ref "J9") (pin "15") (pinfunction "NC2_15") (pintype "passive+no_connect"))
    )
    (net (code "72") (name "unconnected-(J9B-NC4-Pad17)") (class "Default")
      (node (ref "J9") (pin "17") (pinfunction "NC4_17") (pintype "passive+no_connect"))
    )
    (net (code "73") (name "unconnected-(J9B-NC5-Pad18)") (class "Default")
      (node (ref "J9") (pin "18") (pinfunction "NC5_18") (pintype "passive+no_connect"))
    )
  )
)
